# LP_ECG_Pheripherals-X01.net
KiCad netlist of a schematic drawn in Altium Designer
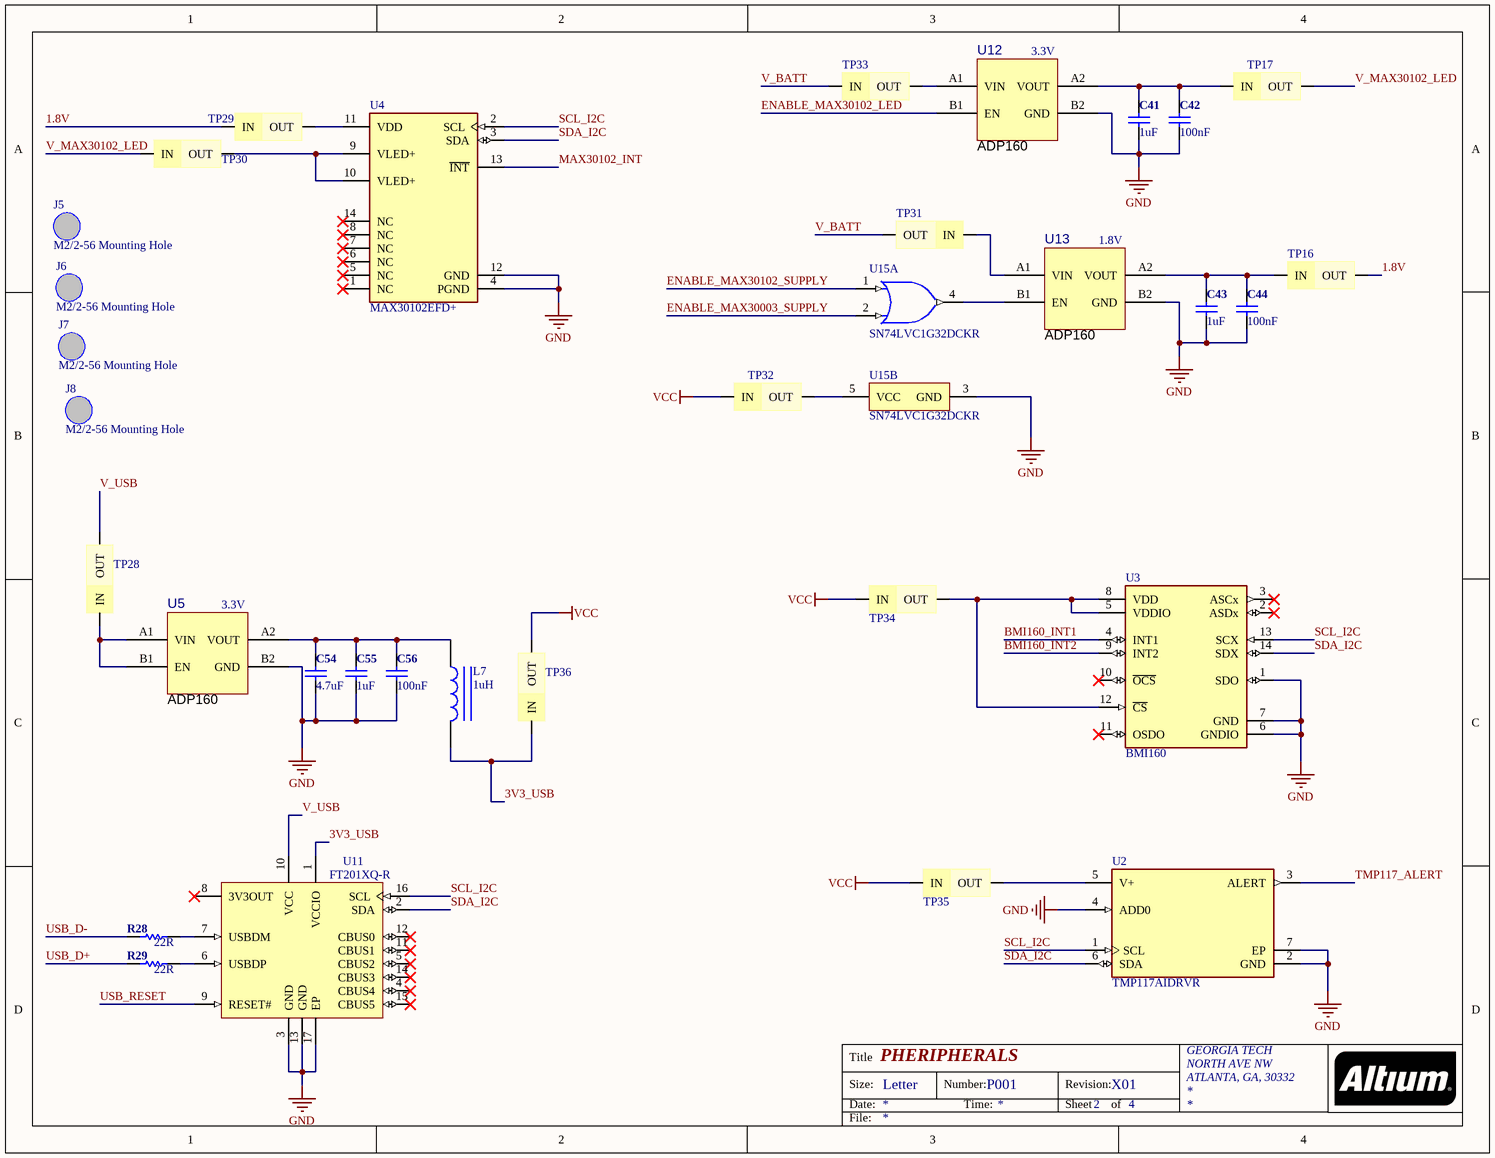
[diagram p0: LP_ECG_Pheripherals-X01.SchDoc]

(export (version "E")
  (design (tool "Eeschema 10.0.6"))
  (components
    (comp (ref "C41")
      (value "1uF")
      (footprint "C0402")
      (fields
        (field (name "MANUFACTURER") "Yageo")
        (field (name "MANUFACTURER PART NUMBER") "CC0402MRX5R5BB105")
        (field (name "TOLERANCE") "20%")
      )
      (libsource (lib "DB-X01") (part "C-0402(1005)"))
    )
    (comp (ref "C42")
      (value "100nF")
      (footprint "C0402")
      (fields
        (field (name "MANUFACTURER") "Taiyo Yuden")
        (field (name "MANUFACTURER PART NUMBER") "TMK105BJ104KV-F")
        (field (name "TOLERANCE") "10%")
      )
      (libsource (lib "DB-X01") (part "C-0402(1005)"))
    )
    (comp (ref "C43")
      (value "1uF")
      (footprint "C0402")
      (fields
        (field (name "MANUFACTURER") "Yageo")
        (field (name "MANUFACTURER PART NUMBER") "CC0402MRX5R5BB105")
        (field (name "TOLERANCE") "20%")
      )
      (libsource (lib "DB-X01") (part "C-0402(1005)"))
    )
    (comp (ref "C44")
      (value "100nF")
      (footprint "C0402")
      (fields
        (field (name "MANUFACTURER") "Taiyo Yuden")
        (field (name "MANUFACTURER PART NUMBER") "TMK105BJ104KV-F")
        (field (name "TOLERANCE") "10%")
      )
      (libsource (lib "DB-X01") (part "C-0402(1005)"))
    )
    (comp (ref "C54")
      (value "4.7uF")
      (footprint "C0402")
      (description "0402 10 V 4.7 uF ±20% Tolerance X5R Multilayer Ceramic Chip Capacitor")
      (fields
        (field (name "MANUFACTURER") "Murata")
        (field (name "MANUFACTURER PART NUMBER") "GRM155R61A475MEAAD")
      )
      (libsource (lib "DB-X01") (part "C-0402(1005)"))
    )
    (comp (ref "C55")
      (value "1uF")
      (footprint "C0402")
      (fields
        (field (name "MANUFACTURER") "Yageo")
        (field (name "MANUFACTURER PART NUMBER") "CC0402MRX5R5BB105")
        (field (name "TOLERANCE") "20%")
      )
      (libsource (lib "DB-X01") (part "C-0402(1005)"))
    )
    (comp (ref "C56")
      (value "100nF")
      (footprint "C0402")
      (fields
        (field (name "MANUFACTURER") "Taiyo Yuden")
        (field (name "MANUFACTURER PART NUMBER") "TMK105BJ104KV-F")
        (field (name "TOLERANCE") "10%")
      )
      (libsource (lib "DB-X01") (part "C-0402(1005)"))
    )
    (comp (ref "J5")
      (value "M2/2-56 Mounting Hole")
      (footprint "Mounting Hole")
      (libsource (lib "DB-X01") (part "M2/2-56 Mounting Hole"))
    )
    (comp (ref "J6")
      (value "M2/2-56 Mounting Hole")
      (footprint "Mounting Hole")
      (libsource (lib "DB-X01") (part "M2/2-56 Mounting Hole"))
    )
    (comp (ref "J7")
      (value "M2/2-56 Mounting Hole")
      (footprint "Mounting Hole")
      (libsource (lib "DB-X01") (part "M2/2-56 Mounting Hole"))
    )
    (comp (ref "J8")
      (value "M2/2-56 Mounting Hole")
      (footprint "Mounting Hole")
      (libsource (lib "DB-X01") (part "M2/2-56 Mounting Hole"))
    )
    (comp (ref "L7")
      (value "1uH")
      (footprint "L0402")
      (description "General Purpose Inductor, 1uH, 20%, 1 Element, Ferrite-Core, SMD, 0402")
      (fields
        (field (name "MANUFACTURER") "TDK")
        (field (name "MANUFACTURER PART NUMBER") "MLZ1005M1R0WT000")
      )
      (libsource (lib "DB-X01") (part "Inductor Iron"))
    )
    (comp (ref "R28")
      (value "22R")
      (footprint "R0402")
      (fields
        (field (name "MANUFACTURER") "Yageo")
        (field (name "MANUFACTURER PART NUMBER") "RC0402JR-0722RL")
        (field (name "TOLERANCE") "5%")
      )
      (libsource (lib "DB-X01") (part "R-0402(1005)"))
    )
    (comp (ref "R29")
      (value "22R")
      (footprint "R0402")
      (fields
        (field (name "MANUFACTURER") "Yageo")
        (field (name "MANUFACTURER PART NUMBER") "RC0402JR-0722RL")
        (field (name "TOLERANCE") "5%")
      )
      (libsource (lib "DB-X01") (part "R-0402(1005)"))
    )
    (comp (ref "TP16")
      (value "JUMPER")
      (footprint "JUMPER")
      (description "SHUNT LP W/HANDLE 2 POS 30AU")
      (fields
        (field (name "MANUFACTURER") "TE Connectivity")
        (field (name "MANUFACTURER PART NUMBER") "8815452")
      )
      (libsource (lib "DB-X01") (part "JUMPER"))
    )
    (comp (ref "TP17")
      (value "JUMPER")
      (footprint "JUMPER")
      (description "SHUNT LP W/HANDLE 2 POS 30AU")
      (fields
        (field (name "MANUFACTURER") "TE Connectivity")
        (field (name "MANUFACTURER PART NUMBER") "8815452")
      )
      (libsource (lib "DB-X01") (part "JUMPER"))
    )
    (comp (ref "TP28")
      (value "JUMPER")
      (footprint "JUMPER")
      (description "SHUNT LP W/HANDLE 2 POS 30AU")
      (fields
        (field (name "MANUFACTURER") "TE Connectivity")
        (field (name "MANUFACTURER PART NUMBER") "8815452")
      )
      (libsource (lib "") (part "JUMPER_1"))
    )
    (comp (ref "TP29")
      (value "JUMPER")
      (footprint "JUMPER")
      (description "SHUNT LP W/HANDLE 2 POS 30AU")
      (fields
        (field (name "MANUFACTURER") "TE Connectivity")
        (field (name "MANUFACTURER PART NUMBER") "8815452")
      )
      (libsource (lib "DB-X02") (part "JUMPER"))
    )
    (comp (ref "TP30")
      (value "JUMPER")
      (footprint "JUMPER")
      (description "SHUNT LP W/HANDLE 2 POS 30AU")
      (fields
        (field (name "MANUFACTURER") "TE Connectivity")
        (field (name "MANUFACTURER PART NUMBER") "8815452")
      )
      (libsource (lib "DB-X02") (part "JUMPER"))
    )
    (comp (ref "TP31")
      (value "JUMPER")
      (footprint "JUMPER")
      (description "SHUNT LP W/HANDLE 2 POS 30AU")
      (fields
        (field (name "MANUFACTURER") "TE Connectivity")
        (field (name "MANUFACTURER PART NUMBER") "8815452")
      )
      (libsource (lib "") (part "JUMPER_2"))
    )
    (comp (ref "TP32")
      (value "JUMPER")
      (footprint "JUMPER")
      (description "SHUNT LP W/HANDLE 2 POS 30AU")
      (fields
        (field (name "MANUFACTURER") "TE Connectivity")
        (field (name "MANUFACTURER PART NUMBER") "8815452")
      )
      (libsource (lib "DB-X02") (part "JUMPER"))
    )
    (comp (ref "TP33")
      (value "JUMPER")
      (footprint "JUMPER")
      (description "SHUNT LP W/HANDLE 2 POS 30AU")
      (fields
        (field (name "MANUFACTURER") "TE Connectivity")
        (field (name "MANUFACTURER PART NUMBER") "8815452")
      )
      (libsource (lib "DB-X02") (part "JUMPER"))
    )
    (comp (ref "TP34")
      (value "JUMPER")
      (footprint "JUMPER")
      (description "SHUNT LP W/HANDLE 2 POS 30AU")
      (fields
        (field (name "MANUFACTURER") "TE Connectivity")
        (field (name "MANUFACTURER PART NUMBER") "8815452")
      )
      (libsource (lib "DB-X02") (part "JUMPER"))
    )
    (comp (ref "TP35")
      (value "JUMPER")
      (footprint "JUMPER")
      (description "SHUNT LP W/HANDLE 2 POS 30AU")
      (fields
        (field (name "MANUFACTURER") "TE Connectivity")
        (field (name "MANUFACTURER PART NUMBER") "8815452")
      )
      (libsource (lib "DB-X02") (part "JUMPER"))
    )
    (comp (ref "TP36")
      (value "JUMPER")
      (footprint "JUMPER")
      (description "SHUNT LP W/HANDLE 2 POS 30AU")
      (fields
        (field (name "MANUFACTURER") "TE Connectivity")
        (field (name "MANUFACTURER PART NUMBER") "8815452")
      )
      (libsource (lib "") (part "JUMPER_1"))
    )
    (comp (ref "U2")
      (value "TMP117AIDRVR")
      (footprint "TMP117AIDRVR")
      (description "TEMPERATURE SENSOR")
      (fields
        (field (name "OCTOPART") "https://octopart.com/tmp117aidrvr-texas+instruments-95511044")
        (field (name "MANUFACTURER") "Texas Instruments")
      )
      (libsource (lib "DB-X01") (part "bceab6869a9cb85cf5675529ee35ce4"))
    )
    (comp (ref "U3")
      (value "BMI160")
      (footprint "FP-BMI160-MFG")
      (description "IMU ACCEL/GYRO I2C/SPI 14LGA")
      (fields (field (name "MANUFACTURER") "Bosch"))
      (libsource (lib "Altium Content Vault") (part "8c6a6e99292f3a8d44c06b20d07aef1"))
    )
    (comp (ref "U4")
      (value "MAX30102EFD+")
      (footprint "FP-F143A5-1-MFG")
      (description "IC SENSOR OXIMETER/HEARTRATE")
      (fields (field (name "MANUFACTURER") "Maxim"))
      (libsource (lib "Altium Content Vault") (part "5fad416c1761f996ad02d0b395f9532"))
    )
    (comp (ref "U5")
      (value "ADP160")
      (footprint "ADP160")
      (description "Fixed Positive LDO Regulator, 3.3V, 0.195V Dropout, CMOS, PBGA4")
      (fields
        (field (name "MANUFACTURER") "Analog Devices")
        (field (name "MANUFACTURER PART NUMBER") "ADP160ACBZ-3.3-R7")
        (field (name "OUTPUT VOLTAGE") "3.3V")
      )
      (libsource (lib "DB-X01") (part "ADP160-3_3V"))
    )
    (comp (ref "U11")
      (value "FT201XQ-R")
      (footprint "QFN-16_N")
      (fields (field (name "MANUFACTURER") "FTDI"))
      (libsource (lib "DB-X01") (part "COM-USB-FT201XQ-SQ17"))
    )
    (comp (ref "U12")
      (value "ADP160")
      (footprint "ADP160")
      (description "Fixed Positive LDO Regulator, 3.3V, 0.195V Dropout, CMOS, PBGA4")
      (fields
        (field (name "MANUFACTURER") "Analog Devices")
        (field (name "MANUFACTURER PART NUMBER") "ADP160ACBZ-3.3-R7")
        (field (name "OUTPUT VOLTAGE") "3.3V")
      )
      (libsource (lib "DB-X01") (part "ADP160-3_3V"))
    )
    (comp (ref "U13")
      (value "ADP160")
      (footprint "ADP160")
      (description "Fixed Positive LDO Regulator, 1.8V, 0.195V Dropout, CMOS, PBGA4")
      (fields
        (field (name "MANUFACTURER") "Analog Devices")
        (field (name "MANUFACTURER PART NUMBER") "ADP160ACBZ-1.8-R7")
        (field (name "OUTPUT VOLTAGE") "1.8V")
      )
      (libsource (lib "DB-X01") (part "ADP160-1_8V"))
    )
    (comp (ref "U15")
      (value "SN74LVC1G32DCKR")
      (footprint "DCK0005A_N")
      (description "Single 2-Input Positive-OR Gate, DCK0005A, LARGE T&R")
      (fields (field (name "MANUFACTURER") "Texas Instruments"))
      (libsource (lib "Altium Content Vault") (part "TI-SN74XXX1X32-5"))
    )
  )
  (nets
    (net (code "1") (name "/1.8V") (class "Default")
      (node (ref "TP16") (pin "2") (pinfunction "OUT_2") (pintype "passive"))
      (node (ref "TP29") (pin "1") (pinfunction "IN_1") (pintype "passive"))
    )
    (net (code "2") (name "/3V3_USB") (class "Default")
      (node (ref "L7") (pin "2") (pinfunction "2_2") (pintype "passive"))
      (node (ref "TP36") (pin "1") (pinfunction "IN_1") (pintype "passive"))
      (node (ref "U11") (pin "1") (pinfunction "VCCIO_1") (pintype "power_in"))
    )
    (net (code "3") (name "/BMI160_INT1") (class "Default")
      (node (ref "U3") (pin "4") (pinfunction "INT1_4") (pintype "bidirectional"))
    )
    (net (code "4") (name "/BMI160_INT2") (class "Default")
      (node (ref "U3") (pin "9") (pinfunction "INT2_9") (pintype "bidirectional"))
    )
    (net (code "5") (name "/ENABLE_MAX30003_SUPPLY") (class "Default")
      (node (ref "U15") (pin "2") (pinfunction "B_2") (pintype "input"))
    )
    (net (code "6") (name "/ENABLE_MAX30102_LED") (class "Default")
      (node (ref "U12") (pin "B1") (pinfunction "EN_B1") (pintype "passive"))
    )
    (net (code "7") (name "/ENABLE_MAX30102_SUPPLY") (class "Default")
      (node (ref "U15") (pin "1") (pinfunction "A_1") (pintype "input"))
    )
    (net (code "8") (name "/MAX30102_INT") (class "Default")
      (node (ref "U4") (pin "13") (pinfunction "~{INT}_13") (pintype "open_collector"))
    )
    (net (code "9") (name "/SCL_I2C") (class "Default")
      (node (ref "U11") (pin "16") (pinfunction "SCL_16") (pintype "input"))
      (node (ref "U2") (pin "1") (pinfunction "SCL_1") (pintype "input"))
      (node (ref "U3") (pin "13") (pinfunction "SCX_13") (pintype "input"))
      (node (ref "U4") (pin "2") (pinfunction "SCL_2") (pintype "input"))
    )
    (net (code "10") (name "/SDA_I2C") (class "Default")
      (node (ref "U11") (pin "2") (pinfunction "SDA_2") (pintype "bidirectional"))
      (node (ref "U2") (pin "6") (pinfunction "SDA_6") (pintype "bidirectional"))
      (node (ref "U3") (pin "14") (pinfunction "SDX_14") (pintype "bidirectional"))
      (node (ref "U4") (pin "3") (pinfunction "SDA_3") (pintype "bidirectional"))
    )
    (net (code "11") (name "/TMP117_ALERT") (class "Default")
      (node (ref "U2") (pin "3") (pinfunction "ALERT_3") (pintype "output"))
    )
    (net (code "12") (name "/USB_D+") (class "Default")
      (node (ref "R29") (pin "1") (pinfunction "1_1") (pintype "passive"))
    )
    (net (code "13") (name "/USB_D-") (class "Default")
      (node (ref "R28") (pin "1") (pinfunction "1_1") (pintype "passive"))
    )
    (net (code "14") (name "/USB_RESET") (class "Default")
      (node (ref "U11") (pin "9") (pinfunction "RESET#_9") (pintype "input"))
    )
    (net (code "15") (name "/V_BATT") (class "Default")
      (node (ref "TP31") (pin "2") (pinfunction "OUT_2") (pintype "passive"))
      (node (ref "TP33") (pin "1") (pinfunction "IN_1") (pintype "passive"))
    )
    (net (code "16") (name "/V_MAX30102_LED") (class "Default")
      (node (ref "TP17") (pin "2") (pinfunction "OUT_2") (pintype "passive"))
      (node (ref "TP30") (pin "1") (pinfunction "IN_1") (pintype "passive"))
    )
    (net (code "17") (name "/V_USB") (class "Default")
      (node (ref "TP28") (pin "2") (pinfunction "OUT_2") (pintype "passive"))
      (node (ref "U11") (pin "10") (pinfunction "VCC_10") (pintype "power_in"))
    )
    (net (code "18") (name "GND") (class "Default")
      (node (ref "C41") (pin "2") (pinfunction "2_2") (pintype "passive"))
      (node (ref "C42") (pin "1") (pinfunction "1_1") (pintype "passive"))
      (node (ref "C43") (pin "2") (pinfunction "2_2") (pintype "passive"))
      (node (ref "C44") (pin "1") (pinfunction "1_1") (pintype "passive"))
      (node (ref "C54") (pin "2") (pinfunction "2_2") (pintype "passive"))
      (node (ref "C55") (pin "2") (pinfunction "2_2") (pintype "passive"))
      (node (ref "C56") (pin "1") (pinfunction "1_1") (pintype "passive"))
      (node (ref "U11") (pin "13") (pinfunction "GND_13") (pintype "power_in"))
      (node (ref "U11") (pin "17") (pinfunction "EP_17") (pintype "power_in"))
      (node (ref "U11") (pin "3") (pinfunction "GND_3") (pintype "power_in"))
      (node (ref "U12") (pin "B2") (pinfunction "GND_B2") (pintype "passive"))
      (node (ref "U13") (pin "B2") (pinfunction "GND_B2") (pintype "passive"))
      (node (ref "U15") (pin "3") (pinfunction "GND_3") (pintype "power_in"))
      (node (ref "U2") (pin "2") (pinfunction "GND_2") (pintype "power_in"))
      (node (ref "U2") (pin "4") (pinfunction "ADD0_4") (pintype "input"))
      (node (ref "U2") (pin "7") (pinfunction "EP_7") (pintype "passive"))
      (node (ref "U3") (pin "1") (pinfunction "SDO_1") (pintype "bidirectional"))
      (node (ref "U3") (pin "6") (pinfunction "GNDIO_6") (pintype "power_in"))
      (node (ref "U3") (pin "7") (pinfunction "GND_7") (pintype "power_in"))
      (node (ref "U4") (pin "12") (pinfunction "GND_12") (pintype "power_in"))
      (node (ref "U4") (pin "4") (pinfunction "PGND_4") (pintype "power_in"))
      (node (ref "U5") (pin "B2") (pinfunction "GND_B2") (pintype "passive"))
    )
    (net (code "19") (name "Net-(TP16-IN)") (class "Default")
      (node (ref "C43") (pin "1") (pinfunction "1_1") (pintype "passive"))
      (node (ref "C44") (pin "2") (pinfunction "2_2") (pintype "passive"))
      (node (ref "TP16") (pin "1") (pinfunction "IN_1") (pintype "passive"))
      (node (ref "U13") (pin "A2") (pinfunction "VOUT_A2") (pintype "passive"))
    )
    (net (code "20") (name "Net-(TP17-IN)") (class "Default")
      (node (ref "C41") (pin "1") (pinfunction "1_1") (pintype "passive"))
      (node (ref "C42") (pin "2") (pinfunction "2_2") (pintype "passive"))
      (node (ref "TP17") (pin "1") (pinfunction "IN_1") (pintype "passive"))
      (node (ref "U12") (pin "A2") (pinfunction "VOUT_A2") (pintype "passive"))
    )
    (net (code "21") (name "Net-(TP28-IN)") (class "Default")
      (node (ref "TP28") (pin "1") (pinfunction "IN_1") (pintype "passive"))
      (node (ref "U5") (pin "A1") (pinfunction "VIN_A1") (pintype "passive"))
      (node (ref "U5") (pin "B1") (pinfunction "EN_B1") (pintype "passive"))
    )
    (net (code "22") (name "Net-(TP29-OUT)") (class "Default")
      (node (ref "TP29") (pin "2") (pinfunction "OUT_2") (pintype "passive"))
      (node (ref "U4") (pin "11") (pinfunction "VDD_11") (pintype "power_in"))
    )
    (net (code "23") (name "Net-(TP30-OUT)") (class "Default")
      (node (ref "TP30") (pin "2") (pinfunction "OUT_2") (pintype "passive"))
      (node (ref "U4") (pin "10") (pinfunction "VLED+_10") (pintype "power_in"))
      (node (ref "U4") (pin "9") (pinfunction "VLED+_9") (pintype "power_in"))
    )
    (net (code "24") (name "Net-(TP31-IN)") (class "Default")
      (node (ref "TP31") (pin "1") (pinfunction "IN_1") (pintype "passive"))
      (node (ref "U13") (pin "A1") (pinfunction "VIN_A1") (pintype "passive"))
    )
    (net (code "25") (name "Net-(TP32-OUT)") (class "Default")
      (node (ref "TP32") (pin "2") (pinfunction "OUT_2") (pintype "passive"))
      (node (ref "U15") (pin "5") (pinfunction "VCC_5") (pintype "power_in"))
    )
    (net (code "26") (name "Net-(TP33-OUT)") (class "Default")
      (node (ref "TP33") (pin "2") (pinfunction "OUT_2") (pintype "passive"))
      (node (ref "U12") (pin "A1") (pinfunction "VIN_A1") (pintype "passive"))
    )
    (net (code "27") (name "Net-(TP34-OUT)") (class "Default")
      (node (ref "TP34") (pin "2") (pinfunction "OUT_2") (pintype "passive"))
      (node (ref "U3") (pin "12") (pinfunction "~{CS}_12") (pintype "input"))
      (node (ref "U3") (pin "5") (pinfunction "VDDIO_5") (pintype "power_in"))
      (node (ref "U3") (pin "8") (pinfunction "VDD_8") (pintype "power_in"))
    )
    (net (code "28") (name "Net-(TP35-OUT)") (class "Default")
      (node (ref "TP35") (pin "2") (pinfunction "OUT_2") (pintype "passive"))
      (node (ref "U2") (pin "5") (pinfunction "V+_5") (pintype "power_in"))
    )
    (net (code "29") (name "Net-(U5-VOUT)") (class "Default")
      (node (ref "C54") (pin "1") (pinfunction "1_1") (pintype "passive"))
      (node (ref "C55") (pin "1") (pinfunction "1_1") (pintype "passive"))
      (node (ref "C56") (pin "2") (pinfunction "2_2") (pintype "passive"))
      (node (ref "L7") (pin "1") (pinfunction "1_1") (pintype "passive"))
      (node (ref "U5") (pin "A2") (pinfunction "VOUT_A2") (pintype "passive"))
    )
    (net (code "30") (name "Net-(U11-USBDM)") (class "Default")
      (node (ref "R28") (pin "2") (pinfunction "2_2") (pintype "passive"))
      (node (ref "U11") (pin "7") (pinfunction "USBDM_7") (pintype "input"))
    )
    (net (code "31") (name "Net-(U11-USBDP)") (class "Default")
      (node (ref "R29") (pin "2") (pinfunction "2_2") (pintype "passive"))
      (node (ref "U11") (pin "6") (pinfunction "USBDP_6") (pintype "input"))
    )
    (net (code "32") (name "Net-(U13-EN)") (class "Default")
      (node (ref "U13") (pin "B1") (pinfunction "EN_B1") (pintype "passive"))
      (node (ref "U15") (pin "4") (pinfunction "Y_4") (pintype "output"))
    )
    (net (code "33") (name "VCC") (class "Default")
      (node (ref "TP32") (pin "1") (pinfunction "IN_1") (pintype "passive"))
      (node (ref "TP34") (pin "1") (pinfunction "IN_1") (pintype "passive"))
      (node (ref "TP35") (pin "1") (pinfunction "IN_1") (pintype "passive"))
      (node (ref "TP36") (pin "2") (pinfunction "OUT_2") (pintype "passive"))
    )
    (net (code "34") (name "unconnected-(U3-ASCx-Pad3)") (class "Default")
      (node (ref "U3") (pin "3") (pinfunction "ASCx_3") (pintype "output+no_connect"))
    )
    (net (code "35") (name "unconnected-(U3-ASDx-Pad2)") (class "Default")
      (node (ref "U3") (pin "2") (pinfunction "ASDx_2") (pintype "bidirectional+no_connect"))
    )
    (net (code "36") (name "unconnected-(U3-OSDO-Pad11)") (class "Default")
      (node (ref "U3") (pin "11") (pinfunction "OSDO_11") (pintype "bidirectional+no_connect"))
    )
    (net (code "37") (name "unconnected-(U3-~{OCS}-Pad10)") (class "Default")
      (node (ref "U3") (pin "10") (pinfunction "~{OCS}_10") (pintype "bidirectional+no_connect"))
    )
    (net (code "38") (name "unconnected-(U4-NC-Pad1)") (class "Default")
      (node (ref "U4") (pin "1") (pinfunction "NC_1") (pintype "passive+no_connect"))
    )
    (net (code "39") (name "unconnected-(U4-NC-Pad5)") (class "Default")
      (node (ref "U4") (pin "5") (pinfunction "NC_5") (pintype "passive+no_connect"))
    )
    (net (code "40") (name "unconnected-(U4-NC-Pad6)") (class "Default")
      (node (ref "U4") (pin "6") (pinfunction "NC_6") (pintype "passive+no_connect"))
    )
    (net (code "41") (name "unconnected-(U4-NC-Pad7)") (class "Default")
      (node (ref "U4") (pin "7") (pinfunction "NC_7") (pintype "passive+no_connect"))
    )
    (net (code "42") (name "unconnected-(U4-NC-Pad8)") (class "Default")
      (node (ref "U4") (pin "8") (pinfunction "NC_8") (pintype "passive+no_connect"))
    )
    (net (code "43") (name "unconnected-(U4-NC-Pad14)") (class "Default")
      (node (ref "U4") (pin "14") (pinfunction "NC_14") (pintype "passive+no_connect"))
    )
    (net (code "44") (name "unconnected-(U11-3V3OUT-Pad8)") (class "Default")
      (node (ref "U11") (pin "8") (pinfunction "3V3OUT_8") (pintype "power_in+no_connect"))
    )
    (net (code "45") (name "unconnected-(U11-CBUS0-Pad12)") (class "Default")
      (node (ref "U11") (pin "12") (pinfunction "CBUS0_12") (pintype "bidirectional+no_connect"))
    )
    (net (code "46") (name "unconnected-(U11-CBUS1-Pad11)") (class "Default")
      (node (ref "U11") (pin "11") (pinfunction "CBUS1_11") (pintype "bidirectional+no_connect"))
    )
    (net (code "47") (name "unconnected-(U11-CBUS2-Pad5)") (class "Default")
      (node (ref "U11") (pin "5") (pinfunction "CBUS2_5") (pintype "bidirectional+no_connect"))
    )
    (net (code "48") (name "unconnected-(U11-CBUS3-Pad14)") (class "Default")
      (node (ref "U11") (pin "14") (pinfunction "CBUS3_14") (pintype "bidirectional+no_connect"))
    )
    (net (code "49") (name "unconnected-(U11-CBUS4-Pad4)") (class "Default")
      (node (ref "U11") (pin "4") (pinfunction "CBUS4_4") (pintype "bidirectional+no_connect"))
    )
    (net (code "50") (name "unconnected-(U11-CBUS5-Pad15)") (class "Default")
      (node (ref "U11") (pin "15") (pinfunction "CBUS5_15") (pintype "bidirectional+no_connect"))
    )
  )
)
